# Sheet2.net
KiCad netlist of a schematic drawn in Altium Designer
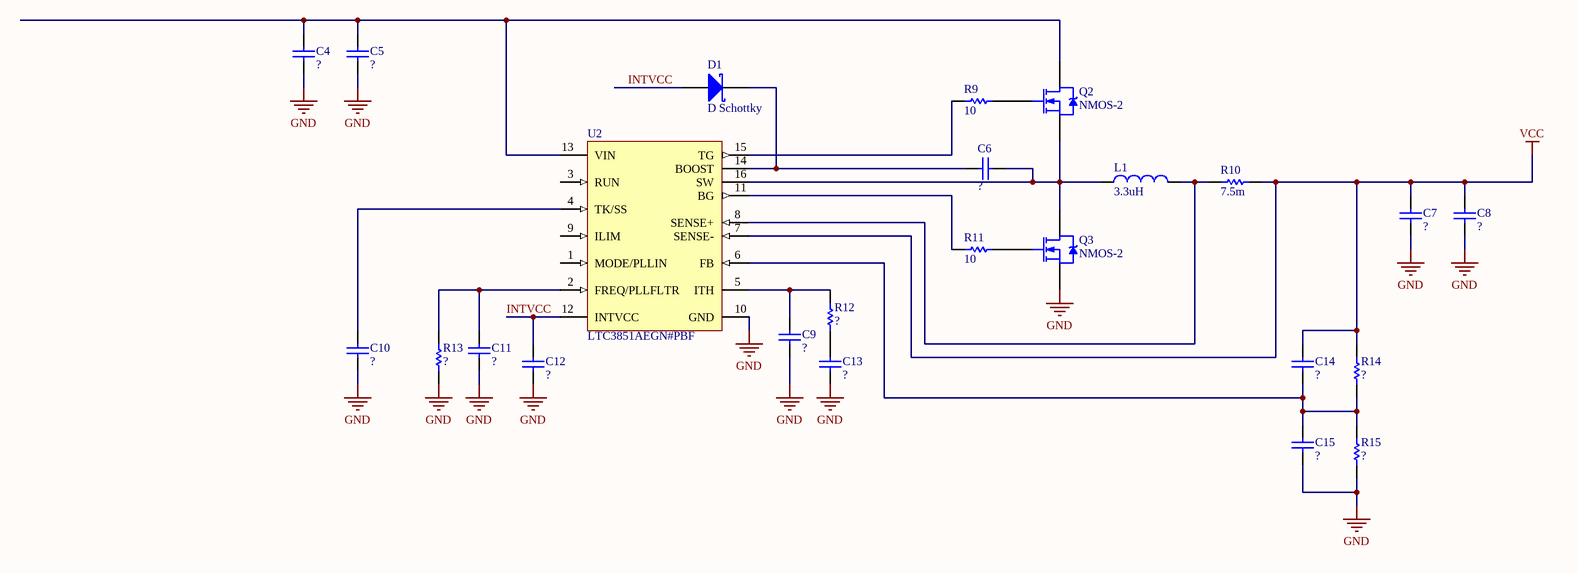
[diagram p0: Sheet2.SchDoc]

(export (version "E")
  (design (tool "Eeschema 10.0.6"))
  (components
    (comp (ref "C4")
      (value "?")
      (footprint "RAD-0.3")
      (description "Capacitor")
      (fields (field (name "Comment") "Cap") (field (name "PUBLISHER") "Altium Limited"))
      (libsource (lib "Miscellaneous Devices") (part "Cap"))
    )
    (comp (ref "C5")
      (value "?")
      (footprint "RAD-0.3")
      (description "Capacitor")
      (fields (field (name "Comment") "Cap") (field (name "PUBLISHER") "Altium Limited"))
      (libsource (lib "Miscellaneous Devices") (part "Cap"))
    )
    (comp (ref "C6")
      (value "?")
      (footprint "RAD-0.3")
      (description "Capacitor")
      (fields (field (name "Comment") "Cap") (field (name "PUBLISHER") "Altium Limited"))
      (libsource (lib "Miscellaneous Devices") (part "Cap"))
    )
    (comp (ref "C7")
      (value "?")
      (footprint "RAD-0.3")
      (description "Capacitor")
      (fields (field (name "Comment") "Cap") (field (name "PUBLISHER") "Altium Limited"))
      (libsource (lib "Miscellaneous Devices") (part "Cap"))
    )
    (comp (ref "C8")
      (value "?")
      (footprint "RAD-0.3")
      (description "Capacitor")
      (fields (field (name "Comment") "Cap") (field (name "PUBLISHER") "Altium Limited"))
      (libsource (lib "Miscellaneous Devices") (part "Cap"))
    )
    (comp (ref "C9")
      (value "?")
      (footprint "RAD-0.3")
      (description "Capacitor")
      (fields (field (name "Comment") "Cap") (field (name "PUBLISHER") "Altium Limited"))
      (libsource (lib "Miscellaneous Devices") (part "Cap"))
    )
    (comp (ref "C10")
      (value "?")
      (footprint "RAD-0.3")
      (description "Capacitor")
      (fields (field (name "Comment") "Cap") (field (name "PUBLISHER") "Altium Limited"))
      (libsource (lib "Miscellaneous Devices") (part "Cap"))
    )
    (comp (ref "C11")
      (value "?")
      (footprint "RAD-0.3")
      (description "Capacitor")
      (fields (field (name "Comment") "Cap") (field (name "PUBLISHER") "Altium Limited"))
      (libsource (lib "Miscellaneous Devices") (part "Cap"))
    )
    (comp (ref "C12")
      (value "?")
      (footprint "RAD-0.3")
      (description "Capacitor")
      (fields (field (name "Comment") "Cap") (field (name "PUBLISHER") "Altium Limited"))
      (libsource (lib "Miscellaneous Devices") (part "Cap"))
    )
    (comp (ref "C13")
      (value "?")
      (footprint "RAD-0.3")
      (description "Capacitor")
      (fields (field (name "Comment") "Cap") (field (name "PUBLISHER") "Altium Limited"))
      (libsource (lib "Miscellaneous Devices") (part "Cap"))
    )
    (comp (ref "C14")
      (value "?")
      (footprint "RAD-0.3")
      (description "Capacitor")
      (fields (field (name "Comment") "Cap") (field (name "PUBLISHER") "Altium Limited"))
      (libsource (lib "Miscellaneous Devices") (part "Cap"))
    )
    (comp (ref "C15")
      (value "?")
      (footprint "RAD-0.3")
      (description "Capacitor")
      (fields (field (name "Comment") "Cap") (field (name "PUBLISHER") "Altium Limited"))
      (libsource (lib "Miscellaneous Devices") (part "Cap"))
    )
    (comp (ref "D1")
      (value "D Schottky")
      (footprint "SMB")
      (description "Schottky Diode")
      (fields (field (name "PUBLISHER") "Altium Limited"))
      (libsource (lib "Miscellaneous Devices") (part "D Schottky"))
    )
    (comp (ref "L1")
      (value "3.3uH")
      (footprint "0402-A")
      (description "Inductor")
      (fields (field (name "PUBLISHER") "Altium Limited"))
      (libsource (lib "Miscellaneous Devices") (part "Inductor"))
    )
    (comp (ref "Q2")
      (value "NMOS-2")
      (footprint "TO-220AB")
      (description "N-Channel Power MOSFET")
      (fields (field (name "PUBLISHER") "Altium Limited"))
      (libsource (lib "Miscellaneous Devices") (part "NMOS-2"))
    )
    (comp (ref "Q3")
      (value "NMOS-2")
      (footprint "TO-220AB")
      (description "N-Channel Power MOSFET")
      (fields (field (name "PUBLISHER") "Altium Limited"))
      (libsource (lib "Miscellaneous Devices") (part "NMOS-2"))
    )
    (comp (ref "R9")
      (value "10")
      (footprint "AXIAL-0.3")
      (description "Resistor")
      (fields (field (name "Comment") "Res1") (field (name "PUBLISHER") "Altium Limited"))
      (libsource (lib "Miscellaneous Devices") (part "Res1"))
    )
    (comp (ref "R10")
      (value "7.5m")
      (footprint "AXIAL-0.3")
      (description "Resistor")
      (fields (field (name "Comment") "Res1") (field (name "PUBLISHER") "Altium Limited"))
      (libsource (lib "Miscellaneous Devices") (part "Res1"))
    )
    (comp (ref "R11")
      (value "10")
      (footprint "AXIAL-0.3")
      (description "Resistor")
      (fields (field (name "Comment") "Res1") (field (name "PUBLISHER") "Altium Limited"))
      (libsource (lib "Miscellaneous Devices") (part "Res1"))
    )
    (comp (ref "R12")
      (value "?")
      (footprint "AXIAL-0.3")
      (description "Resistor")
      (fields (field (name "Comment") "Res1") (field (name "PUBLISHER") "Altium Limited"))
      (libsource (lib "Miscellaneous Devices") (part "Res1"))
    )
    (comp (ref "R13")
      (value "?")
      (footprint "AXIAL-0.3")
      (description "Resistor")
      (fields (field (name "Comment") "Res1") (field (name "PUBLISHER") "Altium Limited"))
      (libsource (lib "Miscellaneous Devices") (part "Res1"))
    )
    (comp (ref "R14")
      (value "?")
      (footprint "AXIAL-0.3")
      (description "Resistor")
      (fields (field (name "Comment") "Res1") (field (name "PUBLISHER") "Altium Limited"))
      (libsource (lib "Miscellaneous Devices") (part "Res1"))
    )
    (comp (ref "R15")
      (value "?")
      (footprint "AXIAL-0.3")
      (description "Resistor")
      (fields (field (name "Comment") "Res1") (field (name "PUBLISHER") "Altium Limited"))
      (libsource (lib "Miscellaneous Devices") (part "Res1"))
    )
    (comp (ref "U2")
      (value "LTC3851AEGN#PBF")
      (footprint "LT-GN-16_L")
      (fields (field (name "MANUFACTURER") "Linear Technology"))
      (libsource (lib "Altium Content Vault") (part "LT-LTC3851_3851A-GN-16"))
    )
  )
  (nets
    (net (code "1") (name "/INTVCC") (class "Default")
      (node (ref "C12") (pin "2") (pinfunction "2_2") (pintype "passive"))
      (node (ref "D1") (pin "1") (pinfunction "A_1") (pintype "passive"))
      (node (ref "U2") (pin "12") (pinfunction "INTVCC_12") (pintype "power_in"))
    )
    (net (code "2") (name "GND") (class "Default")
      (node (ref "C10") (pin "1") (pinfunction "1_1") (pintype "passive"))
      (node (ref "C11") (pin "1") (pinfunction "1_1") (pintype "passive"))
      (node (ref "C12") (pin "1") (pinfunction "1_1") (pintype "passive"))
      (node (ref "C13") (pin "1") (pinfunction "1_1") (pintype "passive"))
      (node (ref "C15") (pin "1") (pinfunction "1_1") (pintype "passive"))
      (node (ref "C4") (pin "1") (pinfunction "1_1") (pintype "passive"))
      (node (ref "C5") (pin "1") (pinfunction "1_1") (pintype "passive"))
      (node (ref "C7") (pin "1") (pinfunction "1_1") (pintype "passive"))
      (node (ref "C8") (pin "1") (pinfunction "1_1") (pintype "passive"))
      (node (ref "C9") (pin "1") (pinfunction "1_1") (pintype "passive"))
      (node (ref "Q3") (pin "3") (pinfunction "S_3") (pintype "passive"))
      (node (ref "R13") (pin "1") (pinfunction "1_1") (pintype "passive"))
      (node (ref "R15") (pin "1") (pinfunction "1_1") (pintype "passive"))
      (node (ref "U2") (pin "10") (pinfunction "GND_10") (pintype "power_in"))
    )
    (net (code "3") (name "Net-(C13-Pad2)") (class "Default")
      (node (ref "C13") (pin "2") (pinfunction "2_2") (pintype "passive"))
      (node (ref "R12") (pin "1") (pinfunction "1_1") (pintype "passive"))
    )
    (net (code "4") (name "Net-(D1-K)") (class "Default")
      (node (ref "C6") (pin "2") (pinfunction "2_2") (pintype "passive"))
      (node (ref "D1") (pin "2") (pinfunction "K_2") (pintype "passive"))
      (node (ref "U2") (pin "14") (pinfunction "BOOST_14") (pintype "passive"))
    )
    (net (code "5") (name "Net-(Q2-D)") (class "Default")
      (node (ref "C4") (pin "2") (pinfunction "2_2") (pintype "passive"))
      (node (ref "C5") (pin "2") (pinfunction "2_2") (pintype "passive"))
      (node (ref "Q2") (pin "2") (pinfunction "D_2") (pintype "passive"))
      (node (ref "U2") (pin "13") (pinfunction "VIN_13") (pintype "power_in"))
    )
    (net (code "6") (name "Net-(Q2-G)") (class "Default")
      (node (ref "Q2") (pin "1") (pinfunction "G_1") (pintype "passive"))
      (node (ref "R9") (pin "1") (pinfunction "1_1") (pintype "passive"))
    )
    (net (code "7") (name "Net-(Q2-S)") (class "Default")
      (node (ref "C6") (pin "1") (pinfunction "1_1") (pintype "passive"))
      (node (ref "L1") (pin "1") (pinfunction "1_1") (pintype "passive"))
      (node (ref "Q2") (pin "3") (pinfunction "S_3") (pintype "passive"))
      (node (ref "Q3") (pin "2") (pinfunction "D_2") (pintype "passive"))
      (node (ref "U2") (pin "16") (pinfunction "SW_16") (pintype "passive"))
    )
    (net (code "8") (name "Net-(Q3-G)") (class "Default")
      (node (ref "Q3") (pin "1") (pinfunction "G_1") (pintype "passive"))
      (node (ref "R11") (pin "1") (pinfunction "1_1") (pintype "passive"))
    )
    (net (code "9") (name "Net-(U2-BG)") (class "Default")
      (node (ref "R11") (pin "2") (pinfunction "2_2") (pintype "passive"))
      (node (ref "U2") (pin "11") (pinfunction "BG_11") (pintype "output"))
    )
    (net (code "10") (name "Net-(U2-FB)") (class "Default")
      (node (ref "C14") (pin "1") (pinfunction "1_1") (pintype "passive"))
      (node (ref "C15") (pin "2") (pinfunction "2_2") (pintype "passive"))
      (node (ref "R14") (pin "1") (pinfunction "1_1") (pintype "passive"))
      (node (ref "R15") (pin "2") (pinfunction "2_2") (pintype "passive"))
      (node (ref "U2") (pin "6") (pinfunction "FB_6") (pintype "input"))
    )
    (net (code "11") (name "Net-(U2-FREQ{slash}PLLFLTR)") (class "Default")
      (node (ref "C11") (pin "2") (pinfunction "2_2") (pintype "passive"))
      (node (ref "R13") (pin "2") (pinfunction "2_2") (pintype "passive"))
      (node (ref "U2") (pin "2") (pinfunction "FREQ/PLLFLTR_2") (pintype "input"))
    )
    (net (code "12") (name "Net-(U2-ITH)") (class "Default")
      (node (ref "C9") (pin "2") (pinfunction "2_2") (pintype "passive"))
      (node (ref "R12") (pin "2") (pinfunction "2_2") (pintype "passive"))
      (node (ref "U2") (pin "5") (pinfunction "ITH_5") (pintype "passive"))
    )
    (net (code "13") (name "Net-(U2-SENSE+)") (class "Default")
      (node (ref "L1") (pin "2") (pinfunction "2_2") (pintype "passive"))
      (node (ref "R10") (pin "2") (pinfunction "2_2") (pintype "passive"))
      (node (ref "U2") (pin "8") (pinfunction "SENSE+_8") (pintype "input"))
    )
    (net (code "14") (name "Net-(U2-TG)") (class "Default")
      (node (ref "R9") (pin "2") (pinfunction "2_2") (pintype "passive"))
      (node (ref "U2") (pin "15") (pinfunction "TG_15") (pintype "output"))
    )
    (net (code "15") (name "Net-(U2-TK{slash}SS)") (class "Default")
      (node (ref "C10") (pin "2") (pinfunction "2_2") (pintype "passive"))
      (node (ref "U2") (pin "4") (pinfunction "TK/SS_4") (pintype "input"))
    )
    (net (code "16") (name "VCC") (class "Default")
      (node (ref "C14") (pin "2") (pinfunction "2_2") (pintype "passive"))
      (node (ref "C7") (pin "2") (pinfunction "2_2") (pintype "passive"))
      (node (ref "C8") (pin "2") (pinfunction "2_2") (pintype "passive"))
      (node (ref "R10") (pin "1") (pinfunction "1_1") (pintype "passive"))
      (node (ref "R14") (pin "2") (pinfunction "2_2") (pintype "passive"))
      (node (ref "U2") (pin "7") (pinfunction "SENSE-_7") (pintype "input"))
    )
    (net (code "17") (name "unconnected-(U2-ILIM-Pad9)") (class "Default")
      (node (ref "U2") (pin "9") (pinfunction "ILIM_9") (pintype "input"))
    )
    (net (code "18") (name "unconnected-(U2-MODE{slash}PLLIN-Pad1)") (class "Default")
      (node (ref "U2") (pin "1") (pinfunction "MODE/PLLIN_1") (pintype "input"))
    )
    (net (code "19") (name "unconnected-(U2-RUN-Pad3)") (class "Default")
      (node (ref "U2") (pin "3") (pinfunction "RUN_3") (pintype "input"))
    )
  )
)
